# SHDN-BSPD-S10-V00-ShutdownRelay.net
KiCad netlist of a schematic drawn in Altium Designer
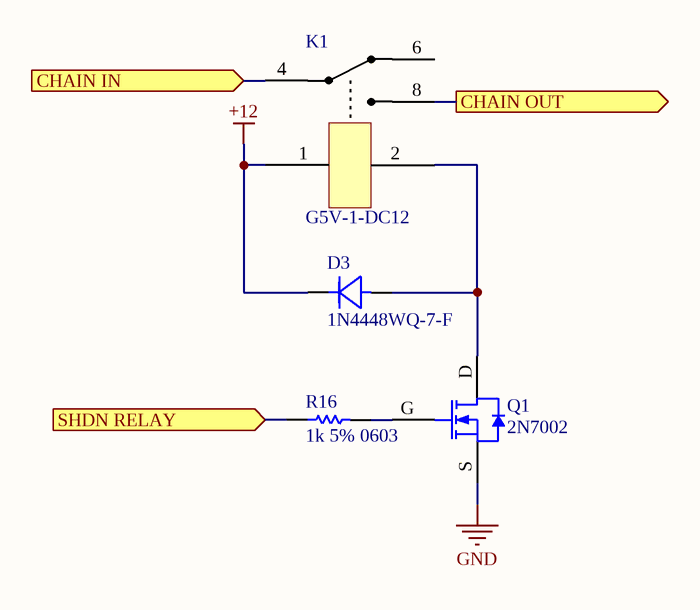
[diagram p0: SHDN-BSPD-S10-V00-ShutdownRelay.SchDoc]

(export (version "E")
  (design (tool "Eeschema 10.0.6"))
  (components
    (comp (ref "D3")
      (value "1N4448WQ-7-F")
      (footprint "SMA")
      (description "Diode, SMD, 75V, 5%, 250mA, SOD123")
      (fields
        (field (name "MANUFACTURER") "ON Semiconductor / Fairchild")
        (field (name "MANUFACTURER PART NUMBER") "1N914BWS")
      )
      (libsource (lib "QUTMS_DiodeLibrary") (part "1N4448WQ-7-F"))
    )
    (comp (ref "K1")
      (value "G5V-1-DC12")
      (footprint "G5V-1")
      (description "General Purpose Relay SPDT (1 Form C) Through Hole, 12V, 2A")
      (libsource (lib "QUTMS_RelayLibrary") (part "G5V-1-DC12"))
    )
    (comp (ref "Q1")
      (value "2N7002")
      (footprint "SOT23-3")
      (libsource (lib "QUTMS_MOSFETLibrary") (part "2N7002"))
    )
    (comp (ref "R16")
      (value "1k 5% 0603")
      (footprint "Res_ThinFilm_0603")
      (description "Resistor, SMD, 1k, 0.1W, 5%, 0603")
      (libsource (lib "StandardResistors") (part "1k 5% 0603"))
    )
  )
  (nets
    (net (code "1") (name "+12") (class "Default")
      (node (ref "D3") (pin "K") (pinfunction "Cathode_K") (pintype "passive"))
      (node (ref "K1") (pin "1") (pinfunction "1_1") (pintype "passive"))
    )
    (net (code "2") (name "/CHAIN IN") (class "Default")
      (node (ref "K1") (pin "4") (pinfunction "4_4") (pintype "passive"))
    )
    (net (code "3") (name "/CHAIN OUT") (class "Default")
      (node (ref "K1") (pin "8") (pinfunction "8_8") (pintype "passive"))
    )
    (net (code "4") (name "/SHDN RELAY") (class "Default")
      (node (ref "R16") (pin "1") (pinfunction "1_1") (pintype "passive"))
    )
    (net (code "5") (name "GND") (class "Default")
      (node (ref "Q1") (pin "S") (pinfunction "S_S") (pintype "passive"))
    )
    (net (code "6") (name "Net-(D3-Anode)") (class "Default")
      (node (ref "D3") (pin "A") (pinfunction "Anode_A") (pintype "passive"))
      (node (ref "K1") (pin "2") (pinfunction "2_2") (pintype "passive"))
      (node (ref "Q1") (pin "D") (pinfunction "D_D") (pintype "passive"))
    )
    (net (code "7") (name "Net-(Q1-PadG)") (class "Default")
      (node (ref "Q1") (pin "G") (pinfunction "G_G") (pintype "passive"))
      (node (ref "R16") (pin "2") (pinfunction "2_2") (pintype "passive"))
    )
    (net (code "8") (name "unconnected-(K1-Pad6)") (class "Default")
      (node (ref "K1") (pin "6") (pinfunction "6_6") (pintype "passive"))
    )
  )
)
